# MainControlUnit_schematic.net
KiCad netlist of a schematic drawn in EasyEDA
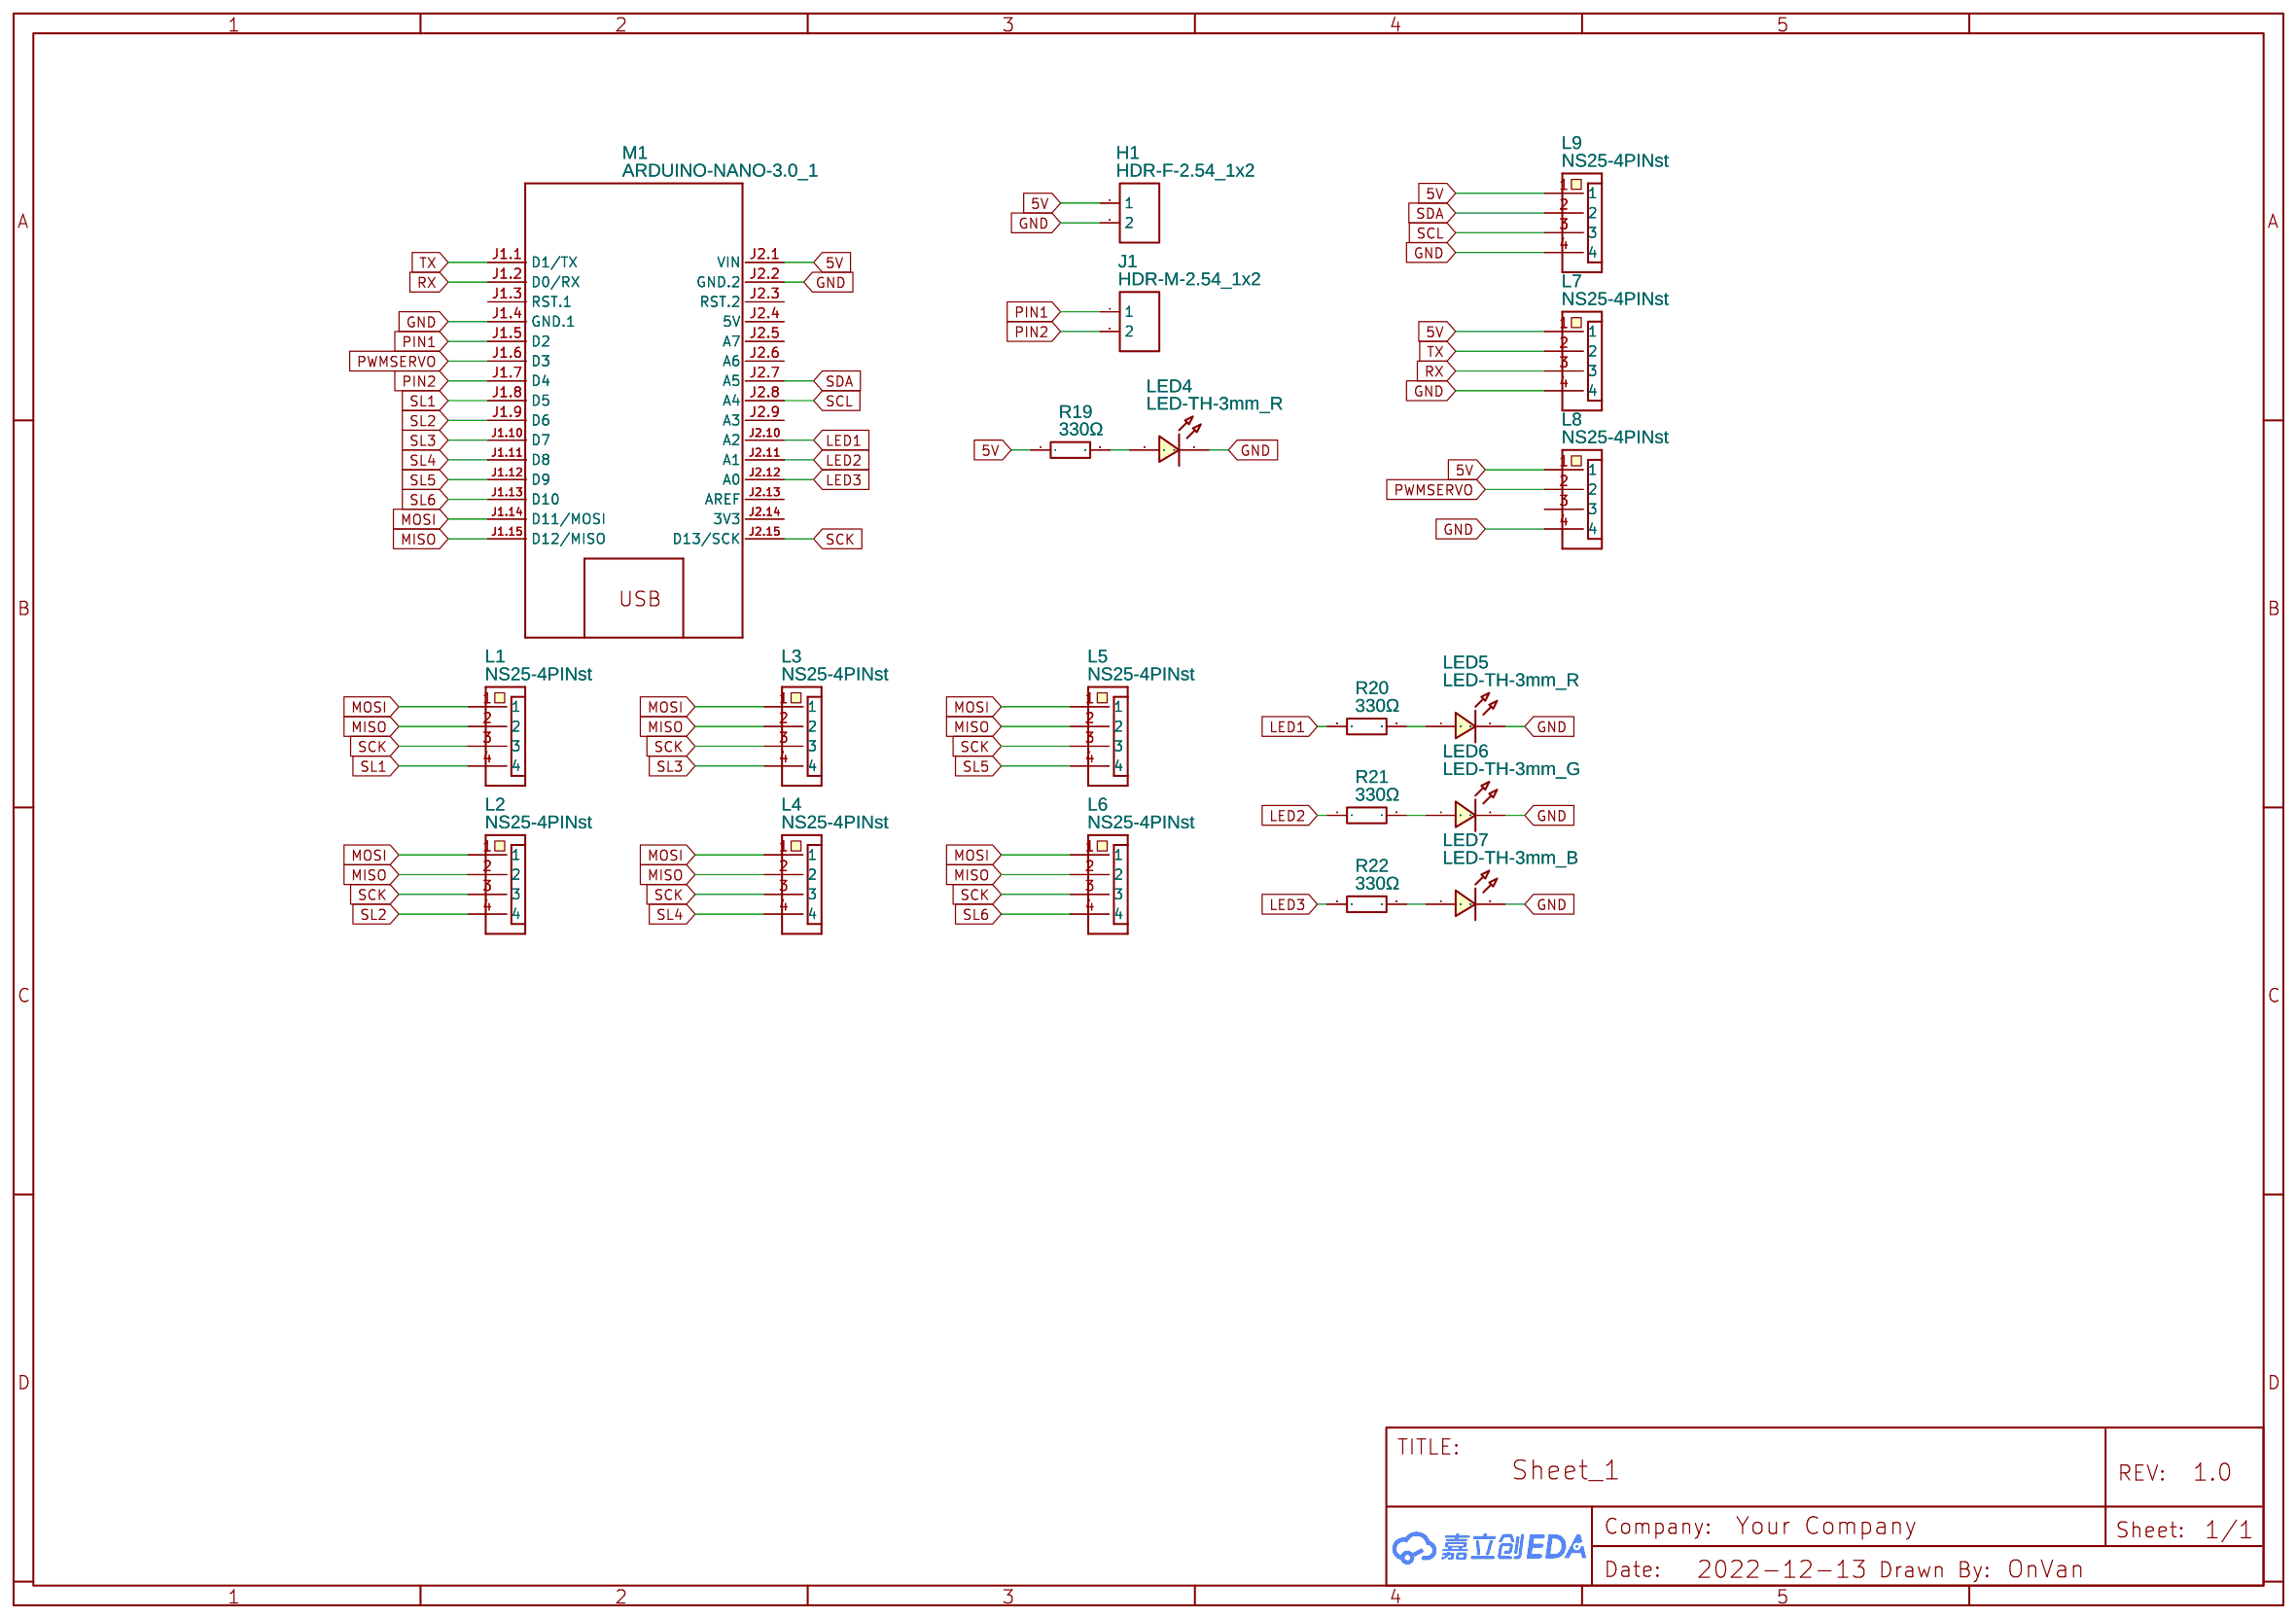
[diagram p0: schematic sheet]

(export (version "E")
  (design (tool "Eeschema 10.0.6"))
  (components
    (comp (ref "H1") (value "HDR-F-2.54_1x2") (libsource (lib "") (part "HDR-F-2.54_1x2")))
    (comp (ref "J1") (value "HDR-M-2.54_1x2") (libsource (lib "") (part "HDR-M-2.54_1x2")))
    (comp (ref "L1") (value "NS25-4PINst") (libsource (lib "") (part "NS25-4PINst")))
    (comp (ref "L2") (value "NS25-4PINst") (libsource (lib "") (part "NS25-4PINst")))
    (comp (ref "L3") (value "NS25-4PINst") (libsource (lib "") (part "NS25-4PINst")))
    (comp (ref "L4") (value "NS25-4PINst") (libsource (lib "") (part "NS25-4PINst")))
    (comp (ref "L5") (value "NS25-4PINst") (libsource (lib "") (part "NS25-4PINst")))
    (comp (ref "L6") (value "NS25-4PINst") (libsource (lib "") (part "NS25-4PINst")))
    (comp (ref "L7") (value "NS25-4PINst") (libsource (lib "") (part "NS25-4PINst")))
    (comp (ref "L8") (value "NS25-4PINst") (libsource (lib "") (part "NS25-4PINst")))
    (comp (ref "L9") (value "NS25-4PINst") (libsource (lib "") (part "NS25-4PINst")))
    (comp (ref "LED4")
      (value "LED-TH-3mm_R")
      (fields
        (field (name "Manufacturer Part") "204-10SDRD/S530-A3-L")
        (field (name "Manufacturer") "EVERLIGHT(台湾亿光)")
      )
      (libsource (lib "") (part "LED-TH-3mm_R"))
    )
    (comp (ref "LED5")
      (value "LED-TH-3mm_R")
      (fields
        (field (name "Manufacturer Part") "204-10SDRD/S530-A3-L")
        (field (name "Manufacturer") "EVERLIGHT(台湾亿光)")
      )
      (libsource (lib "") (part "LED-TH-3mm_R"))
    )
    (comp (ref "LED6")
      (value "LED-TH-3mm_G")
      (fields
        (field (name "Manufacturer Part") "204-10SYGD/S530-E3")
        (field (name "Manufacturer") "EVERLIGHT(台湾亿光)")
      )
      (libsource (lib "") (part "LED-TH-3mm_G"))
    )
    (comp (ref "LED7")
      (value "LED-TH-3mm_B")
      (fields
        (field (name "Manufacturer Part") "204-10SUBC/S400-A4")
        (field (name "Manufacturer") "EVERLIGHT(台湾亿光)")
      )
      (libsource (lib "") (part "LED-TH-3mm_B"))
    )
    (comp (ref "M1") (value "ARDUINO-NANO-3.0_1") (libsource (lib "") (part "ARDUINO-NANO-3.0_1")))
    (comp (ref "R19")
      (value "330Ω")
      (fields (field (name "Manufacturer Part") "MFR0W4F3300A50") (field (name "Manufacturer") "UniOhm"))
      (libsource (lib "") (part "MFR0W4F3300A50"))
    )
    (comp (ref "R20")
      (value "330Ω")
      (fields (field (name "Manufacturer Part") "MFR0W4F2200A50") (field (name "Manufacturer") "UniOhm"))
      (libsource (lib "") (part "120Ω"))
    )
    (comp (ref "R21")
      (value "330Ω")
      (fields (field (name "Manufacturer Part") "MFR0W4F2200A50") (field (name "Manufacturer") "UniOhm"))
      (libsource (lib "") (part "120Ω"))
    )
    (comp (ref "R22")
      (value "330Ω")
      (fields (field (name "Manufacturer Part") "MFR0W4F2200A50") (field (name "Manufacturer") "UniOhm"))
      (libsource (lib "") (part "120Ω"))
    )
  )
  (nets
    (net (code "1") (name "5V") (class "Default")
      (node (ref "H1") (pin "1") (pinfunction "1_1") (pintype "input"))
      (node (ref "L7") (pin "1") (pinfunction "1_1") (pintype "bidirectional"))
      (node (ref "L8") (pin "1") (pinfunction "1_1") (pintype "bidirectional"))
      (node (ref "L9") (pin "1") (pinfunction "1_1") (pintype "bidirectional"))
      (node (ref "M1") (pin "J2.1") (pinfunction "VIN_J2.1") (pintype "bidirectional"))
      (node (ref "R19") (pin "1") (pinfunction "1_1") (pintype "input"))
    )
    (net (code "2") (name "GND") (class "Default")
      (node (ref "H1") (pin "2") (pinfunction "2_2") (pintype "input"))
      (node (ref "L7") (pin "4") (pinfunction "4_4") (pintype "bidirectional"))
      (node (ref "L8") (pin "4") (pinfunction "4_4") (pintype "bidirectional"))
      (node (ref "L9") (pin "4") (pinfunction "4_4") (pintype "bidirectional"))
      (node (ref "LED4") (pin "2") (pinfunction "2_2") (pintype "unspecified"))
      (node (ref "LED5") (pin "2") (pinfunction "2_2") (pintype "unspecified"))
      (node (ref "LED6") (pin "2") (pinfunction "2_2") (pintype "unspecified"))
      (node (ref "LED7") (pin "2") (pinfunction "2_2") (pintype "unspecified"))
      (node (ref "M1") (pin "J1.4") (pinfunction "GND.1_J1.4") (pintype "bidirectional"))
      (node (ref "M1") (pin "J2.2") (pinfunction "GND.2_J2.2") (pintype "bidirectional"))
    )
    (net (code "3") (name "LED1") (class "Default")
      (node (ref "M1") (pin "J2.10") (pinfunction "A2_J2.10") (pintype "bidirectional"))
      (node (ref "R20") (pin "1") (pinfunction "1_1") (pintype "input"))
    )
    (net (code "4") (name "LED2") (class "Default")
      (node (ref "M1") (pin "J2.11") (pinfunction "A1_J2.11") (pintype "bidirectional"))
      (node (ref "R21") (pin "1") (pinfunction "1_1") (pintype "input"))
    )
    (net (code "5") (name "LED3") (class "Default")
      (node (ref "M1") (pin "J2.12") (pinfunction "A0_J2.12") (pintype "bidirectional"))
      (node (ref "R22") (pin "1") (pinfunction "1_1") (pintype "input"))
    )
    (net (code "6") (name "MISO") (class "Default")
      (node (ref "L1") (pin "2") (pinfunction "2_2") (pintype "bidirectional"))
      (node (ref "L2") (pin "2") (pinfunction "2_2") (pintype "bidirectional"))
      (node (ref "L3") (pin "2") (pinfunction "2_2") (pintype "bidirectional"))
      (node (ref "L4") (pin "2") (pinfunction "2_2") (pintype "bidirectional"))
      (node (ref "L5") (pin "2") (pinfunction "2_2") (pintype "bidirectional"))
      (node (ref "L6") (pin "2") (pinfunction "2_2") (pintype "bidirectional"))
      (node (ref "M1") (pin "J1.15") (pinfunction "D12/MISO_J1.15") (pintype "bidirectional"))
    )
    (net (code "7") (name "MOSI") (class "Default")
      (node (ref "L1") (pin "1") (pinfunction "1_1") (pintype "bidirectional"))
      (node (ref "L2") (pin "1") (pinfunction "1_1") (pintype "bidirectional"))
      (node (ref "L3") (pin "1") (pinfunction "1_1") (pintype "bidirectional"))
      (node (ref "L4") (pin "1") (pinfunction "1_1") (pintype "bidirectional"))
      (node (ref "L5") (pin "1") (pinfunction "1_1") (pintype "bidirectional"))
      (node (ref "L6") (pin "1") (pinfunction "1_1") (pintype "bidirectional"))
      (node (ref "M1") (pin "J1.14") (pinfunction "D11/MOSI_J1.14") (pintype "bidirectional"))
    )
    (net (code "8") (name "Net-(LED4-Pad1)") (class "Default")
      (node (ref "LED4") (pin "1") (pinfunction "1_1") (pintype "unspecified"))
      (node (ref "R19") (pin "2") (pinfunction "2_2") (pintype "input"))
    )
    (net (code "9") (name "Net-(LED5-Pad1)") (class "Default")
      (node (ref "LED5") (pin "1") (pinfunction "1_1") (pintype "unspecified"))
      (node (ref "R20") (pin "2") (pinfunction "2_2") (pintype "input"))
    )
    (net (code "10") (name "Net-(LED6-Pad1)") (class "Default")
      (node (ref "LED6") (pin "1") (pinfunction "1_1") (pintype "unspecified"))
      (node (ref "R21") (pin "2") (pinfunction "2_2") (pintype "input"))
    )
    (net (code "11") (name "Net-(LED7-Pad1)") (class "Default")
      (node (ref "LED7") (pin "1") (pinfunction "1_1") (pintype "unspecified"))
      (node (ref "R22") (pin "2") (pinfunction "2_2") (pintype "input"))
    )
    (net (code "12") (name "PIN1") (class "Default")
      (node (ref "J1") (pin "1") (pinfunction "1_1") (pintype "unspecified"))
      (node (ref "M1") (pin "J1.5") (pinfunction "D2_J1.5") (pintype "bidirectional"))
    )
    (net (code "13") (name "PIN2") (class "Default")
      (node (ref "J1") (pin "2") (pinfunction "2_2") (pintype "unspecified"))
      (node (ref "M1") (pin "J1.7") (pinfunction "D4_J1.7") (pintype "bidirectional"))
    )
    (net (code "14") (name "PWMSERVO") (class "Default")
      (node (ref "L8") (pin "2") (pinfunction "2_2") (pintype "bidirectional"))
      (node (ref "M1") (pin "J1.6") (pinfunction "D3_J1.6") (pintype "bidirectional"))
    )
    (net (code "15") (name "RX") (class "Default")
      (node (ref "L7") (pin "3") (pinfunction "3_3") (pintype "bidirectional"))
      (node (ref "M1") (pin "J1.2") (pinfunction "D0/RX_J1.2") (pintype "bidirectional"))
    )
    (net (code "16") (name "SCK") (class "Default")
      (node (ref "L1") (pin "3") (pinfunction "3_3") (pintype "bidirectional"))
      (node (ref "L2") (pin "3") (pinfunction "3_3") (pintype "bidirectional"))
      (node (ref "L3") (pin "3") (pinfunction "3_3") (pintype "bidirectional"))
      (node (ref "L4") (pin "3") (pinfunction "3_3") (pintype "bidirectional"))
      (node (ref "L5") (pin "3") (pinfunction "3_3") (pintype "bidirectional"))
      (node (ref "L6") (pin "3") (pinfunction "3_3") (pintype "bidirectional"))
      (node (ref "M1") (pin "J2.15") (pinfunction "D13/SCK_J2.15") (pintype "bidirectional"))
    )
    (net (code "17") (name "SCL") (class "Default")
      (node (ref "L9") (pin "3") (pinfunction "3_3") (pintype "bidirectional"))
      (node (ref "M1") (pin "J2.8") (pinfunction "A4_J2.8") (pintype "bidirectional"))
    )
    (net (code "18") (name "SDA") (class "Default")
      (node (ref "L9") (pin "2") (pinfunction "2_2") (pintype "bidirectional"))
      (node (ref "M1") (pin "J2.7") (pinfunction "A5_J2.7") (pintype "bidirectional"))
    )
    (net (code "19") (name "SL1") (class "Default")
      (node (ref "L1") (pin "4") (pinfunction "4_4") (pintype "bidirectional"))
      (node (ref "M1") (pin "J1.8") (pinfunction "D5_J1.8") (pintype "bidirectional"))
    )
    (net (code "20") (name "SL2") (class "Default")
      (node (ref "L2") (pin "4") (pinfunction "4_4") (pintype "bidirectional"))
      (node (ref "M1") (pin "J1.9") (pinfunction "D6_J1.9") (pintype "bidirectional"))
    )
    (net (code "21") (name "SL3") (class "Default")
      (node (ref "L3") (pin "4") (pinfunction "4_4") (pintype "bidirectional"))
      (node (ref "M1") (pin "J1.10") (pinfunction "D7_J1.10") (pintype "bidirectional"))
    )
    (net (code "22") (name "SL4") (class "Default")
      (node (ref "L4") (pin "4") (pinfunction "4_4") (pintype "bidirectional"))
      (node (ref "M1") (pin "J1.11") (pinfunction "D8_J1.11") (pintype "bidirectional"))
    )
    (net (code "23") (name "SL5") (class "Default")
      (node (ref "L5") (pin "4") (pinfunction "4_4") (pintype "bidirectional"))
      (node (ref "M1") (pin "J1.12") (pinfunction "D9_J1.12") (pintype "bidirectional"))
    )
    (net (code "24") (name "SL6") (class "Default")
      (node (ref "L6") (pin "4") (pinfunction "4_4") (pintype "bidirectional"))
      (node (ref "M1") (pin "J1.13") (pinfunction "D10_J1.13") (pintype "bidirectional"))
    )
    (net (code "25") (name "TX") (class "Default")
      (node (ref "L7") (pin "2") (pinfunction "2_2") (pintype "bidirectional"))
      (node (ref "M1") (pin "J1.1") (pinfunction "D1/TX_J1.1") (pintype "bidirectional"))
    )
    (net (code "26") (name "unconnected-(L8-Pad3)") (class "Default")
      (node (ref "L8") (pin "3") (pinfunction "3_3") (pintype "bidirectional"))
    )
    (net (code "27") (name "unconnected-(M1-3V3-PadJ2.14)") (class "Default")
      (node (ref "M1") (pin "J2.14") (pinfunction "3V3_J2.14") (pintype "bidirectional"))
    )
    (net (code "28") (name "unconnected-(M1-5V-PadJ2.4)") (class "Default")
      (node (ref "M1") (pin "J2.4") (pinfunction "5V_J2.4") (pintype "bidirectional"))
    )
    (net (code "29") (name "unconnected-(M1-A3-PadJ2.9)") (class "Default")
      (node (ref "M1") (pin "J2.9") (pinfunction "A3_J2.9") (pintype "bidirectional"))
    )
    (net (code "30") (name "unconnected-(M1-A6-PadJ2.6)") (class "Default")
      (node (ref "M1") (pin "J2.6") (pinfunction "A6_J2.6") (pintype "bidirectional"))
    )
    (net (code "31") (name "unconnected-(M1-A7-PadJ2.5)") (class "Default")
      (node (ref "M1") (pin "J2.5") (pinfunction "A7_J2.5") (pintype "bidirectional"))
    )
    (net (code "32") (name "unconnected-(M1-AREF-PadJ2.13)") (class "Default")
      (node (ref "M1") (pin "J2.13") (pinfunction "AREF_J2.13") (pintype "bidirectional"))
    )
    (net (code "33") (name "unconnected-(M1-RST.1-PadJ1.3)") (class "Default")
      (node (ref "M1") (pin "J1.3") (pinfunction "RST.1_J1.3") (pintype "bidirectional"))
    )
    (net (code "34") (name "unconnected-(M1-RST.2-PadJ2.3)") (class "Default")
      (node (ref "M1") (pin "J2.3") (pinfunction "RST.2_J2.3") (pintype "bidirectional"))
    )
  )
)
